# openTPM-v30.net
KiCad netlist of a schematic drawn in EAGLE
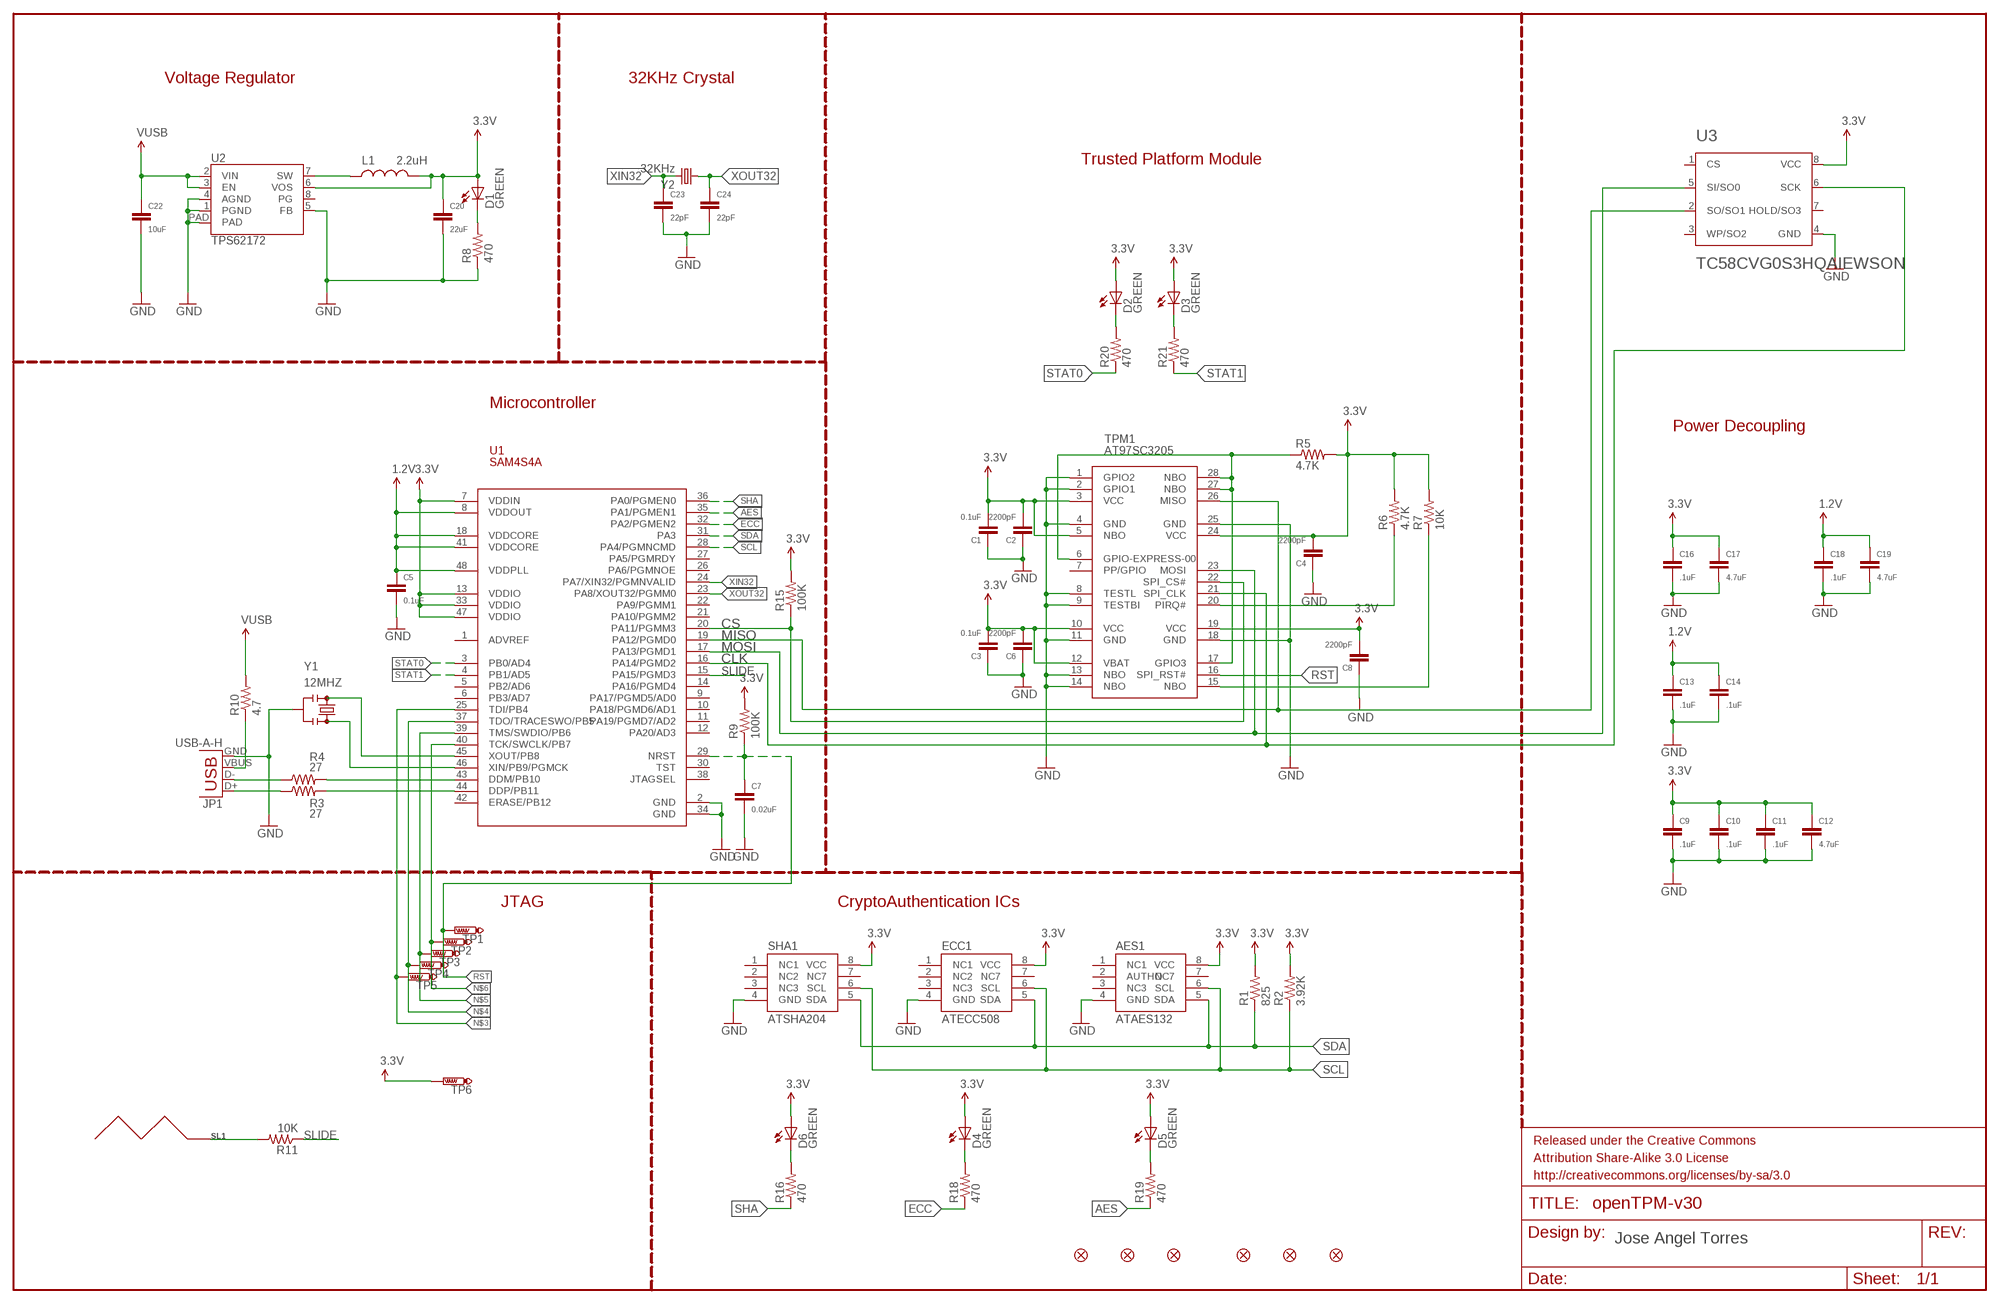
[diagram p0: schematic, sheet 1]

(export (version "E")
  (design (tool "Eeschema 10.0.6"))
  (components
    (comp (ref "AES1")
      (value "ATAES132")
      (footprint "eagle-import:CRYPTOTRONIX_SOIC8")
      (libsource (lib "eagle-import") (part "CRYPTOTRONIX_ATAES132"))
    )
    (comp (ref "C1")
      (value "0.1uF")
      (footprint "eagle-import:0402")
      (libsource (lib "eagle-import") (part "CAPACITOR.0402"))
    )
    (comp (ref "C2")
      (value "2200pF")
      (footprint "eagle-import:0402")
      (libsource (lib "eagle-import") (part "CAPACITOR.0402"))
    )
    (comp (ref "C3")
      (value "0.1uF")
      (footprint "eagle-import:0402")
      (libsource (lib "eagle-import") (part "CAPACITOR.0402"))
    )
    (comp (ref "C4")
      (value "2200pF")
      (footprint "eagle-import:0402")
      (libsource (lib "eagle-import") (part "CAPACITOR.0402"))
    )
    (comp (ref "C5")
      (value "0.1uF")
      (footprint "eagle-import:0402")
      (libsource (lib "eagle-import") (part "CAPACITOR.0402"))
    )
    (comp (ref "C6")
      (value "2200pF")
      (footprint "eagle-import:0402")
      (libsource (lib "eagle-import") (part "CAPACITOR.0402"))
    )
    (comp (ref "C7")
      (value "0.02uF")
      (footprint "eagle-import:0402")
      (libsource (lib "eagle-import") (part "CAPACITOR.0402"))
    )
    (comp (ref "C8")
      (value "2200pF")
      (footprint "eagle-import:0402")
      (libsource (lib "eagle-import") (part "CAPACITOR.0402"))
    )
    (comp (ref "C9")
      (value ".1uF")
      (footprint "eagle-import:0402")
      (libsource (lib "eagle-import") (part "CAPACITOR.0402"))
    )
    (comp (ref "C10")
      (value ".1uF")
      (footprint "eagle-import:0402")
      (libsource (lib "eagle-import") (part "CAPACITOR.0402"))
    )
    (comp (ref "C11")
      (value ".1uF")
      (footprint "eagle-import:0402")
      (libsource (lib "eagle-import") (part "CAPACITOR.0402"))
    )
    (comp (ref "C12")
      (value "4.7uF")
      (footprint "eagle-import:0402")
      (libsource (lib "eagle-import") (part "CAPACITOR.0402"))
    )
    (comp (ref "C13")
      (value ".1uF")
      (footprint "eagle-import:0402")
      (libsource (lib "eagle-import") (part "CAPACITOR.0402"))
    )
    (comp (ref "C14")
      (value ".1uF")
      (footprint "eagle-import:0402")
      (libsource (lib "eagle-import") (part "CAPACITOR.0402"))
    )
    (comp (ref "C16")
      (value ".1uF")
      (footprint "eagle-import:0402")
      (libsource (lib "eagle-import") (part "CAPACITOR.0402"))
    )
    (comp (ref "C17")
      (value "4.7uF")
      (footprint "eagle-import:0402")
      (libsource (lib "eagle-import") (part "CAPACITOR.0402"))
    )
    (comp (ref "C18")
      (value ".1uF")
      (footprint "eagle-import:0402")
      (libsource (lib "eagle-import") (part "CAPACITOR.0402"))
    )
    (comp (ref "C19")
      (value "4.7uF")
      (footprint "eagle-import:0402")
      (libsource (lib "eagle-import") (part "CAPACITOR.0402"))
    )
    (comp (ref "C20")
      (value "22uF")
      (footprint "eagle-import:0603")
      (libsource (lib "eagle-import") (part "CAPACITOR.0603"))
    )
    (comp (ref "C22")
      (value "10uF")
      (footprint "eagle-import:0402")
      (libsource (lib "eagle-import") (part "CAPACITOR.0402"))
    )
    (comp (ref "C23")
      (value "22pF")
      (footprint "eagle-import:0402")
      (libsource (lib "eagle-import") (part "CAPACITOR.0402"))
    )
    (comp (ref "C24")
      (value "22pF")
      (footprint "eagle-import:0402")
      (libsource (lib "eagle-import") (part "CAPACITOR.0402"))
    )
    (comp (ref "D1")
      (value "GREEN")
      (footprint "eagle-import:SPARKFUN-LED_LED-0603")
      (libsource (lib "eagle-import") (part "SPARKFUN-LED_LED-GREEN0603"))
    )
    (comp (ref "D2")
      (value "GREEN")
      (footprint "eagle-import:SPARKFUN-LED_LED-0603")
      (libsource (lib "eagle-import") (part "SPARKFUN-LED_LED-GREEN0603"))
    )
    (comp (ref "D3")
      (value "GREEN")
      (footprint "eagle-import:SPARKFUN-LED_LED-0603")
      (libsource (lib "eagle-import") (part "SPARKFUN-LED_LED-GREEN0603"))
    )
    (comp (ref "D4")
      (value "GREEN")
      (footprint "eagle-import:SPARKFUN-LED_LED-0603")
      (libsource (lib "eagle-import") (part "SPARKFUN-LED_LED-GREEN0603"))
    )
    (comp (ref "D5")
      (value "GREEN")
      (footprint "eagle-import:SPARKFUN-LED_LED-0603")
      (libsource (lib "eagle-import") (part "SPARKFUN-LED_LED-GREEN0603"))
    )
    (comp (ref "D6")
      (value "GREEN")
      (footprint "eagle-import:SPARKFUN-LED_LED-0603")
      (libsource (lib "eagle-import") (part "SPARKFUN-LED_LED-GREEN0603"))
    )
    (comp (ref "ECC1")
      (value "ATECC508")
      (footprint "eagle-import:CRYPTOTRONIX_SOIC8")
      (libsource (lib "eagle-import") (part "ATECC508"))
    )
    (comp (ref "FID1")
      (value "SPARKFUN-AESTHETICS_FIDUCIAL1X2")
      (footprint "eagle-import:SPARKFUN-AESTHETICS_FIDUCIAL-1X2")
      (libsource (lib "eagle-import") (part "SPARKFUN-AESTHETICS_FIDUCIAL1X2"))
    )
    (comp (ref "FID2")
      (value "SPARKFUN-AESTHETICS_FIDUCIAL1X2")
      (footprint "eagle-import:SPARKFUN-AESTHETICS_FIDUCIAL-1X2")
      (libsource (lib "eagle-import") (part "SPARKFUN-AESTHETICS_FIDUCIAL1X2"))
    )
    (comp (ref "FID3")
      (value "SPARKFUN-AESTHETICS_FIDUCIAL1X2")
      (footprint "eagle-import:SPARKFUN-AESTHETICS_FIDUCIAL-1X2")
      (libsource (lib "eagle-import") (part "SPARKFUN-AESTHETICS_FIDUCIAL1X2"))
    )
    (comp (ref "FID4")
      (value "SPARKFUN-AESTHETICS_FIDUCIAL1X2")
      (footprint "eagle-import:SPARKFUN-AESTHETICS_FIDUCIAL-1X2")
      (libsource (lib "eagle-import") (part "SPARKFUN-AESTHETICS_FIDUCIAL1X2"))
    )
    (comp (ref "FID5")
      (value "SPARKFUN-AESTHETICS_FIDUCIAL1X2")
      (footprint "eagle-import:SPARKFUN-AESTHETICS_FIDUCIAL-1X2")
      (libsource (lib "eagle-import") (part "SPARKFUN-AESTHETICS_FIDUCIAL1X2"))
    )
    (comp (ref "FID6")
      (value "SPARKFUN-AESTHETICS_FIDUCIAL1X2")
      (footprint "eagle-import:SPARKFUN-AESTHETICS_FIDUCIAL-1X2")
      (libsource (lib "eagle-import") (part "SPARKFUN-AESTHETICS_FIDUCIAL1X2"))
    )
    (comp (ref "JP1")
      (value "USB-A-H")
      (footprint "eagle-import:USB-A-H")
      (libsource (lib "eagle-import") (part "USB-A-H"))
    )
    (comp (ref "L1")
      (value "2.2uH")
      (footprint "eagle-import:C0402")
      (libsource (lib "eagle-import") (part "INDUCTOR0402"))
    )
    (comp (ref "R1")
      (value "825")
      (footprint "eagle-import:0402")
      (libsource (lib "eagle-import") (part "RESISTOR.0402"))
    )
    (comp (ref "R2")
      (value "3.92K")
      (footprint "eagle-import:0402")
      (libsource (lib "eagle-import") (part "RESISTOR.0402"))
    )
    (comp (ref "R3")
      (value "27")
      (footprint "eagle-import:0402")
      (libsource (lib "eagle-import") (part "RESISTOR.0402"))
    )
    (comp (ref "R4")
      (value "27")
      (footprint "eagle-import:0402")
      (libsource (lib "eagle-import") (part "RESISTOR.0402"))
    )
    (comp (ref "R5")
      (value "4.7K")
      (footprint "eagle-import:0402")
      (libsource (lib "eagle-import") (part "RESISTOR.0402"))
    )
    (comp (ref "R6")
      (value "4.7K")
      (footprint "eagle-import:0402")
      (libsource (lib "eagle-import") (part "RESISTOR.0402"))
    )
    (comp (ref "R7")
      (value "10K")
      (footprint "eagle-import:0402")
      (libsource (lib "eagle-import") (part "RESISTOR.0402"))
    )
    (comp (ref "R8")
      (value "470")
      (footprint "eagle-import:0402")
      (libsource (lib "eagle-import") (part "RESISTOR.0402"))
    )
    (comp (ref "R9")
      (value "100K")
      (footprint "eagle-import:0402")
      (libsource (lib "eagle-import") (part "RESISTOR.0402"))
    )
    (comp (ref "R10")
      (value "4.7")
      (footprint "eagle-import:0402")
      (libsource (lib "eagle-import") (part "RESISTOR.0402"))
    )
    (comp (ref "R11")
      (value "10K")
      (footprint "eagle-import:0402")
      (libsource (lib "eagle-import") (part "RESISTOR.0402"))
    )
    (comp (ref "R15")
      (value "100K")
      (footprint "eagle-import:0402")
      (libsource (lib "eagle-import") (part "RESISTOR.0402"))
    )
    (comp (ref "R16")
      (value "470")
      (footprint "eagle-import:0402")
      (libsource (lib "eagle-import") (part "RESISTOR.0402"))
    )
    (comp (ref "R18")
      (value "470")
      (footprint "eagle-import:0402")
      (libsource (lib "eagle-import") (part "RESISTOR.0402"))
    )
    (comp (ref "R19")
      (value "470")
      (footprint "eagle-import:0402")
      (libsource (lib "eagle-import") (part "RESISTOR.0402"))
    )
    (comp (ref "R20")
      (value "470")
      (footprint "eagle-import:0402")
      (libsource (lib "eagle-import") (part "RESISTOR.0402"))
    )
    (comp (ref "R21")
      (value "470")
      (footprint "eagle-import:0402")
      (libsource (lib "eagle-import") (part "RESISTOR.0402"))
    )
    (comp (ref "SHA1")
      (value "ATSHA204")
      (footprint "eagle-import:CRYPTOTRONIX_SOIC8")
      (libsource (lib "eagle-import") (part "CRYPTOTRONIX_ATSHA204"))
    )
    (comp (ref "SL1")
      (value "SLIDER_PASSIVE_1SEG")
      (footprint "eagle-import:SLIDER_PASSIVE_1SEG_12MM")
      (libsource (lib "eagle-import") (part "SLIDER_PASSIVE_1SEG"))
    )
    (comp (ref "TP1")
      (value "PTR1B1,27")
      (footprint "eagle-import:B1,27")
      (libsource (lib "eagle-import") (part "PTR1B1,27"))
    )
    (comp (ref "TP2")
      (value "PTR1B1,27")
      (footprint "eagle-import:B1,27")
      (libsource (lib "eagle-import") (part "PTR1B1,27"))
    )
    (comp (ref "TP3")
      (value "PTR1B1,27")
      (footprint "eagle-import:B1,27")
      (libsource (lib "eagle-import") (part "PTR1B1,27"))
    )
    (comp (ref "TP4")
      (value "PTR1B1,27")
      (footprint "eagle-import:B1,27")
      (libsource (lib "eagle-import") (part "PTR1B1,27"))
    )
    (comp (ref "TP5")
      (value "PTR1B1,27")
      (footprint "eagle-import:B1,27")
      (libsource (lib "eagle-import") (part "PTR1B1,27"))
    )
    (comp (ref "TP6")
      (value "PTR1B1,27")
      (footprint "eagle-import:B1,27")
      (libsource (lib "eagle-import") (part "PTR1B1,27"))
    )
    (comp (ref "TPM1")
      (value "AT97SC3205")
      (footprint "eagle-import:TSSOP28")
      (libsource (lib "eagle-import") (part "AT97SC3205"))
    )
    (comp (ref "U1")
      (value "SAM4S4A")
      (footprint "eagle-import:LQFP-48")
      (libsource (lib "eagle-import") (part "SAM4S4A"))
    )
    (comp (ref "U2")
      (value "TPS62172")
      (footprint "eagle-import:WSON-8-PAD")
      (libsource (lib "eagle-import") (part "TPS62172"))
    )
    (comp (ref "U3")
      (value "TC58CVG0S3HQAIEWSON")
      (footprint "eagle-import:WSON-8-PAD")
      (libsource (lib "eagle-import") (part "TC58CVG0S3HQAIEWSON"))
    )
    (comp (ref "Y1")
      (value "12MHZ")
      (footprint "eagle-import:RESONATOR-SMD")
      (libsource (lib "eagle-import") (part "RESONATOR12MHZ"))
    )
    (comp (ref "Y2")
      (value "32KHz")
      (footprint "eagle-import:CRYSTAL-32KHZ-SMD_EPSON_MC146")
      (libsource (lib "eagle-import") (part "CRYSTALEPSONMC146"))
    )
  )
  (nets
    (net (code "1") (name "/CLK") (class "Default")
      (node (ref "TPM1") (pin "21") (pinfunction "SPI_CLK_21") (pintype "bidirectional"))
      (node (ref "U1") (pin "16") (pinfunction "PA14/PGMD2_16") (pintype "bidirectional"))
      (node (ref "U3") (pin "6") (pinfunction "SCK_6") (pintype "bidirectional"))
    )
    (net (code "2") (name "/CS") (class "Default")
      (node (ref "R15") (pin "1") (pinfunction "1_1") (pintype "passive"))
      (node (ref "TPM1") (pin "22") (pinfunction "SPI_CS#_22") (pintype "power_in"))
      (node (ref "U1") (pin "20") (pinfunction "PA11/PGMM3_20") (pintype "bidirectional"))
    )
    (net (code "3") (name "/MISO") (class "Default")
      (node (ref "TPM1") (pin "26") (pinfunction "MISO_26") (pintype "power_in"))
      (node (ref "U1") (pin "19") (pinfunction "PA12/PGMD0_19") (pintype "bidirectional"))
      (node (ref "U3") (pin "2") (pinfunction "SO/SO1_2") (pintype "bidirectional"))
    )
    (net (code "4") (name "/MOSI") (class "Default")
      (node (ref "TPM1") (pin "23") (pinfunction "MOSI_23") (pintype "power_in"))
      (node (ref "U1") (pin "17") (pinfunction "PA13/PGMD1_17") (pintype "bidirectional"))
      (node (ref "U3") (pin "5") (pinfunction "SI/SO0_5") (pintype "bidirectional"))
    )
    (net (code "5") (name "/SLIDE") (class "Default")
      (node (ref "R11") (pin "1") (pinfunction "1_1") (pintype "passive"))
      (node (ref "U1") (pin "15") (pinfunction "PA15/PGMD3_15") (pintype "bidirectional"))
    )
    (net (code "6") (name "1.2V") (class "Default")
      (node (ref "C13") (pin "1") (pinfunction "1_1") (pintype "passive"))
      (node (ref "C14") (pin "1") (pinfunction "1_1") (pintype "passive"))
      (node (ref "C18") (pin "1") (pinfunction "1_1") (pintype "passive"))
      (node (ref "C19") (pin "1") (pinfunction "1_1") (pintype "passive"))
      (node (ref "C5") (pin "1") (pinfunction "1_1") (pintype "passive"))
      (node (ref "U1") (pin "18") (pinfunction "VDDCORE_18") (pintype "bidirectional"))
      (node (ref "U1") (pin "41") (pinfunction "VDDCORE_41") (pintype "bidirectional"))
      (node (ref "U1") (pin "48") (pinfunction "VDDPLL_48") (pintype "bidirectional"))
      (node (ref "U1") (pin "8") (pinfunction "VDDOUT_8") (pintype "bidirectional"))
    )
    (net (code "7") (name "3.3V") (class "Default")
      (node (ref "AES1") (pin "8") (pinfunction "VCC_8") (pintype "power_in"))
      (node (ref "C1") (pin "2") (pinfunction "2_2") (pintype "passive"))
      (node (ref "C10") (pin "1") (pinfunction "1_1") (pintype "passive"))
      (node (ref "C11") (pin "1") (pinfunction "1_1") (pintype "passive"))
      (node (ref "C12") (pin "1") (pinfunction "1_1") (pintype "passive"))
      (node (ref "C16") (pin "1") (pinfunction "1_1") (pintype "passive"))
      (node (ref "C17") (pin "1") (pinfunction "1_1") (pintype "passive"))
      (node (ref "C2") (pin "2") (pinfunction "2_2") (pintype "passive"))
      (node (ref "C20") (pin "1") (pinfunction "1_1") (pintype "passive"))
      (node (ref "C3") (pin "2") (pinfunction "2_2") (pintype "passive"))
      (node (ref "C4") (pin "2") (pinfunction "2_2") (pintype "passive"))
      (node (ref "C6") (pin "2") (pinfunction "2_2") (pintype "passive"))
      (node (ref "C8") (pin "2") (pinfunction "2_2") (pintype "passive"))
      (node (ref "C9") (pin "1") (pinfunction "1_1") (pintype "passive"))
      (node (ref "D1") (pin "A") (pinfunction "A_A") (pintype "passive"))
      (node (ref "D2") (pin "A") (pinfunction "A_A") (pintype "passive"))
      (node (ref "D3") (pin "A") (pinfunction "A_A") (pintype "passive"))
      (node (ref "D4") (pin "A") (pinfunction "A_A") (pintype "passive"))
      (node (ref "D5") (pin "A") (pinfunction "A_A") (pintype "passive"))
      (node (ref "D6") (pin "A") (pinfunction "A_A") (pintype "passive"))
      (node (ref "ECC1") (pin "8") (pinfunction "VCC_8") (pintype "power_in"))
      (node (ref "L1") (pin "2") (pinfunction "2_2") (pintype "passive"))
      (node (ref "R1") (pin "2") (pinfunction "2_2") (pintype "passive"))
      (node (ref "R15") (pin "2") (pinfunction "2_2") (pintype "passive"))
      (node (ref "R2") (pin "2") (pinfunction "2_2") (pintype "passive"))
      (node (ref "R5") (pin "2") (pinfunction "2_2") (pintype "passive"))
      (node (ref "R6") (pin "2") (pinfunction "2_2") (pintype "passive"))
      (node (ref "R7") (pin "2") (pinfunction "2_2") (pintype "passive"))
      (node (ref "R9") (pin "2") (pinfunction "2_2") (pintype "passive"))
      (node (ref "SHA1") (pin "8") (pinfunction "VCC_8") (pintype "power_in"))
      (node (ref "TP6") (pin "TP") (pinfunction "TP_TP") (pintype "input"))
      (node (ref "TPM1") (pin "10") (pinfunction "VCC_10") (pintype "power_in"))
      (node (ref "TPM1") (pin "12") (pinfunction "VBAT_12") (pintype "bidirectional"))
      (node (ref "TPM1") (pin "19") (pinfunction "VCC_19") (pintype "power_in"))
      (node (ref "TPM1") (pin "24") (pinfunction "VCC_24") (pintype "power_in"))
      (node (ref "TPM1") (pin "3") (pinfunction "VCC_3") (pintype "power_in"))
      (node (ref "TPM1") (pin "5") (pinfunction "NBO_5") (pintype "bidirectional"))
      (node (ref "U1") (pin "13") (pinfunction "VDDIO_13") (pintype "bidirectional"))
      (node (ref "U1") (pin "33") (pinfunction "VDDIO_33") (pintype "bidirectional"))
      (node (ref "U1") (pin "47") (pinfunction "VDDIO_47") (pintype "bidirectional"))
      (node (ref "U1") (pin "7") (pinfunction "VDDIN_7") (pintype "bidirectional"))
      (node (ref "U2") (pin "6") (pinfunction "VOS_6") (pintype "bidirectional"))
      (node (ref "U3") (pin "8") (pinfunction "VCC_8") (pintype "bidirectional"))
    )
    (net (code "8") (name "AES") (class "Default")
      (node (ref "R19") (pin "1") (pinfunction "1_1") (pintype "passive"))
      (node (ref "U1") (pin "35") (pinfunction "PA1/PGMEN1_35") (pintype "bidirectional"))
    )
    (net (code "9") (name "ECC") (class "Default")
      (node (ref "R18") (pin "1") (pinfunction "1_1") (pintype "passive"))
      (node (ref "U1") (pin "32") (pinfunction "PA2/PGMEN2_32") (pintype "bidirectional"))
    )
    (net (code "10") (name "GND") (class "Default")
      (node (ref "AES1") (pin "4") (pinfunction "GND_4") (pintype "power_in"))
      (node (ref "C1") (pin "1") (pinfunction "1_1") (pintype "passive"))
      (node (ref "C10") (pin "2") (pinfunction "2_2") (pintype "passive"))
      (node (ref "C11") (pin "2") (pinfunction "2_2") (pintype "passive"))
      (node (ref "C12") (pin "2") (pinfunction "2_2") (pintype "passive"))
      (node (ref "C13") (pin "2") (pinfunction "2_2") (pintype "passive"))
      (node (ref "C14") (pin "2") (pinfunction "2_2") (pintype "passive"))
      (node (ref "C16") (pin "2") (pinfunction "2_2") (pintype "passive"))
      (node (ref "C17") (pin "2") (pinfunction "2_2") (pintype "passive"))
      (node (ref "C18") (pin "2") (pinfunction "2_2") (pintype "passive"))
      (node (ref "C19") (pin "2") (pinfunction "2_2") (pintype "passive"))
      (node (ref "C2") (pin "1") (pinfunction "1_1") (pintype "passive"))
      (node (ref "C20") (pin "2") (pinfunction "2_2") (pintype "passive"))
      (node (ref "C22") (pin "2") (pinfunction "2_2") (pintype "passive"))
      (node (ref "C23") (pin "2") (pinfunction "2_2") (pintype "passive"))
      (node (ref "C24") (pin "2") (pinfunction "2_2") (pintype "passive"))
      (node (ref "C3") (pin "1") (pinfunction "1_1") (pintype "passive"))
      (node (ref "C4") (pin "1") (pinfunction "1_1") (pintype "passive"))
      (node (ref "C5") (pin "2") (pinfunction "2_2") (pintype "passive"))
      (node (ref "C6") (pin "1") (pinfunction "1_1") (pintype "passive"))
      (node (ref "C7") (pin "2") (pinfunction "2_2") (pintype "passive"))
      (node (ref "C8") (pin "1") (pinfunction "1_1") (pintype "passive"))
      (node (ref "C9") (pin "2") (pinfunction "2_2") (pintype "passive"))
      (node (ref "ECC1") (pin "4") (pinfunction "GND_4") (pintype "power_in"))
      (node (ref "JP1") (pin "GND") (pinfunction "GND_GND") (pintype "bidirectional"))
      (node (ref "R8") (pin "1") (pinfunction "1_1") (pintype "passive"))
      (node (ref "SHA1") (pin "4") (pinfunction "GND_4") (pintype "power_in"))
      (node (ref "TPM1") (pin "1") (pinfunction "GPIO2_1") (pintype "bidirectional"))
      (node (ref "TPM1") (pin "11") (pinfunction "GND_11") (pintype "power_in"))
      (node (ref "TPM1") (pin "13") (pinfunction "NBO_13") (pintype "bidirectional"))
      (node (ref "TPM1") (pin "14") (pinfunction "NBO_14") (pintype "bidirectional"))
      (node (ref "TPM1") (pin "18") (pinfunction "GND_18") (pintype "power_in"))
      (node (ref "TPM1") (pin "2") (pinfunction "GPIO1_2") (pintype "bidirectional"))
      (node (ref "TPM1") (pin "25") (pinfunction "GND_25") (pintype "power_in"))
      (node (ref "TPM1") (pin "4") (pinfunction "GND_4") (pintype "power_in"))
      (node (ref "TPM1") (pin "8") (pinfunction "TESTL_8") (pintype "bidirectional"))
      (node (ref "TPM1") (pin "9") (pinfunction "TESTBI_9") (pintype "bidirectional"))
      (node (ref "U1") (pin "2") (pinfunction "GND_2") (pintype "bidirectional"))
      (node (ref "U1") (pin "34") (pinfunction "GND_34") (pintype "bidirectional"))
      (node (ref "U2") (pin "1") (pinfunction "PGND_1") (pintype "bidirectional"))
      (node (ref "U2") (pin "4") (pinfunction "AGND_4") (pintype "bidirectional"))
      (node (ref "U2") (pin "5") (pinfunction "FB_5") (pintype "bidirectional"))
      (node (ref "U2") (pin "PAD") (pinfunction "PAD_PAD") (pintype "bidirectional"))
      (node (ref "U3") (pin "4") (pinfunction "GND_4") (pintype "bidirectional"))
      (node (ref "Y1") (pin "2") (pinfunction "2_2") (pintype "passive"))
    )
    (net (code "11") (name "N$3") (class "Default")
      (node (ref "TP5") (pin "TP") (pinfunction "TP_TP") (pintype "input"))
      (node (ref "U1") (pin "25") (pinfunction "TDI/PB4_25") (pintype "bidirectional"))
    )
    (net (code "12") (name "N$4") (class "Default")
      (node (ref "TP4") (pin "TP") (pinfunction "TP_TP") (pintype "input"))
      (node (ref "U1") (pin "37") (pinfunction "TDO/TRACESWO/PB5_37") (pintype "bidirectional"))
    )
    (net (code "13") (name "N$5") (class "Default")
      (node (ref "TP3") (pin "TP") (pinfunction "TP_TP") (pintype "input"))
      (node (ref "U1") (pin "39") (pinfunction "TMS/SWDIO/PB6_39") (pintype "bidirectional"))
    )
    (net (code "14") (name "N$6") (class "Default")
      (node (ref "TP2") (pin "TP") (pinfunction "TP_TP") (pintype "input"))
      (node (ref "U1") (pin "40") (pinfunction "TCK/SWCLK/PB7_40") (pintype "bidirectional"))
    )
    (net (code "15") (name "Net-(D1-PadC)") (class "Default")
      (node (ref "D1") (pin "C") (pinfunction "C_C") (pintype "passive"))
      (node (ref "R8") (pin "2") (pinfunction "2_2") (pintype "passive"))
    )
    (net (code "16") (name "Net-(D2-PadC)") (class "Default")
      (node (ref "D2") (pin "C") (pinfunction "C_C") (pintype "passive"))
      (node (ref "R20") (pin "2") (pinfunction "2_2") (pintype "passive"))
    )
    (net (code "17") (name "Net-(D3-PadC)") (class "Default")
      (node (ref "D3") (pin "C") (pinfunction "C_C") (pintype "passive"))
      (node (ref "R21") (pin "2") (pinfunction "2_2") (pintype "passive"))
    )
    (net (code "18") (name "Net-(D4-PadC)") (class "Default")
      (node (ref "D4") (pin "C") (pinfunction "C_C") (pintype "passive"))
      (node (ref "R18") (pin "2") (pinfunction "2_2") (pintype "passive"))
    )
    (net (code "19") (name "Net-(D5-PadC)") (class "Default")
      (node (ref "D5") (pin "C") (pinfunction "C_C") (pintype "passive"))
      (node (ref "R19") (pin "2") (pinfunction "2_2") (pintype "passive"))
    )
    (net (code "20") (name "Net-(D6-PadC)") (class "Default")
      (node (ref "D6") (pin "C") (pinfunction "C_C") (pintype "passive"))
      (node (ref "R16") (pin "2") (pinfunction "2_2") (pintype "passive"))
    )
    (net (code "21") (name "Net-(JP1-PadD+)") (class "Default")
      (node (ref "JP1") (pin "D+") (pinfunction "D+_D+") (pintype "bidirectional"))
      (node (ref "R3") (pin "1") (pinfunction "1_1") (pintype "passive"))
    )
    (net (code "22") (name "Net-(JP1-PadD-)") (class "Default")
      (node (ref "JP1") (pin "D-") (pinfunction "D-_D-") (pintype "bidirectional"))
      (node (ref "R4") (pin "1") (pinfunction "1_1") (pintype "passive"))
    )
    (net (code "23") (name "Net-(JP1-PadVBUS)") (class "Default")
      (node (ref "JP1") (pin "VBUS") (pinfunction "VBUS_VBUS") (pintype "bidirectional"))
      (node (ref "R10") (pin "1") (pinfunction "1_1") (pintype "passive"))
    )
    (net (code "24") (name "Net-(R7-Pad1)") (class "Default")
      (node (ref "R7") (pin "1") (pinfunction "1_1") (pintype "passive"))
      (node (ref "TPM1") (pin "15") (pinfunction "NBO_15") (pintype "bidirectional"))
    )
    (net (code "25") (name "Net-(SL1-SL1)") (class "Default")
      (node (ref "R11") (pin "2") (pinfunction "2_2") (pintype "passive"))
      (node (ref "SL1") (pin "S1") (pinfunction "SL1_S1") (pintype "passive"))
    )
    (net (code "26") (name "Net-(TPM1-GPIO-EXPRESS-00)") (class "Default")
      (node (ref "R5") (pin "1") (pinfunction "1_1") (pintype "passive"))
      (node (ref "TPM1") (pin "17") (pinfunction "GPIO3_17") (pintype "power_in"))
      (node (ref "TPM1") (pin "27") (pinfunction "NBO_27") (pintype "bidirectional"))
      (node (ref "TPM1") (pin "28") (pinfunction "NBO_28") (pintype "bidirectional"))
      (node (ref "TPM1") (pin "6") (pinfunction "GPIO-EXPRESS-00_6") (pintype "power_in"))
    )
    (net (code "27") (name "Net-(TPM1-PIRQ#)") (class "Default")
      (node (ref "R6") (pin "1") (pinfunction "1_1") (pintype "passive"))
      (node (ref "TPM1") (pin "20") (pinfunction "PIRQ#_20") (pintype "power_in"))
    )
    (net (code "28") (name "Net-(U1-DDM{slash}PB10)") (class "Default")
      (node (ref "R4") (pin "2") (pinfunction "2_2") (pintype "passive"))
      (node (ref "U1") (pin "43") (pinfunction "DDM/PB10_43") (pintype "bidirectional"))
    )
    (net (code "29") (name "Net-(U1-DDP{slash}PB11)") (class "Default")
      (node (ref "R3") (pin "2") (pinfunction "2_2") (pintype "passive"))
      (node (ref "U1") (pin "44") (pinfunction "DDP/PB11_44") (pintype "bidirectional"))
    )
    (net (code "30") (name "Net-(U1-XIN{slash}PB9{slash}PGMCK)") (class "Default")
      (node (ref "U1") (pin "46") (pinfunction "XIN/PB9/PGMCK_46") (pintype "bidirectional"))
      (node (ref "Y1") (pin "3") (pinfunction "3_3") (pintype "passive"))
    )
    (net (code "31") (name "Net-(U1-XOUT{slash}PB8)") (class "Default")
      (node (ref "U1") (pin "45") (pinfunction "XOUT/PB8_45") (pintype "bidirectional"))
      (node (ref "Y1") (pin "1") (pinfunction "1_1") (pintype "passive"))
    )
    (net (code "32") (name "Net-(U2-SW)") (class "Default")
      (node (ref "L1") (pin "1") (pinfunction "1_1") (pintype "passive"))
      (node (ref "U2") (pin "7") (pinfunction "SW_7") (pintype "bidirectional"))
    )
    (net (code "33") (name "RST") (class "Default")
      (node (ref "C7") (pin "1") (pinfunction "1_1") (pintype "passive"))
      (node (ref "R9") (pin "1") (pinfunction "1_1") (pintype "passive"))
      (node (ref "TP1") (pin "TP") (pinfunction "TP_TP") (pintype "input"))
      (node (ref "TPM1") (pin "16") (pinfunction "SPI_RST#_16") (pintype "bidirectional"))
      (node (ref "U1") (pin "29") (pinfunction "NRST_29") (pintype "bidirectional"))
    )
    (net (code "34") (name "SCL") (class "Default")
      (node (ref "AES1") (pin "6") (pinfunction "SCL_6") (pintype "bidirectional"))
      (node (ref "ECC1") (pin "6") (pinfunction "SCL_6") (pintype "bidirectional"))
      (node (ref "R2") (pin "1") (pinfunction "1_1") (pintype "passive"))
      (node (ref "SHA1") (pin "6") (pinfunction "SCL_6") (pintype "bidirectional"))
      (node (ref "U1") (pin "28") (pinfunction "PA4/PGMNCMD_28") (pintype "bidirectional"))
    )
    (net (code "35") (name "SDA") (class "Default")
      (node (ref "AES1") (pin "5") (pinfunction "SDA_5") (pintype "bidirectional"))
      (node (ref "ECC1") (pin "5") (pinfunction "SDA_5") (pintype "bidirectional"))
      (node (ref "R1") (pin "1") (pinfunction "1_1") (pintype "passive"))
      (node (ref "SHA1") (pin "5") (pinfunction "SDA_5") (pintype "bidirectional"))
      (node (ref "U1") (pin "31") (pinfunction "PA3_31") (pintype "bidirectional"))
    )
    (net (code "36") (name "SHA") (class "Default")
      (node (ref "R16") (pin "1") (pinfunction "1_1") (pintype "passive"))
      (node (ref "U1") (pin "36") (pinfunction "PA0/PGMEN0_36") (pintype "bidirectional"))
    )
    (net (code "37") (name "STAT0") (class "Default")
      (node (ref "R20") (pin "1") (pinfunction "1_1") (pintype "passive"))
      (node (ref "U1") (pin "3") (pinfunction "PB0/AD4_3") (pintype "bidirectional"))
    )
    (net (code "38") (name "STAT1") (class "Default")
      (node (ref "R21") (pin "1") (pinfunction "1_1") (pintype "passive"))
      (node (ref "U1") (pin "4") (pinfunction "PB1/AD5_4") (pintype "bidirectional"))
    )
    (net (code "39") (name "VUSB") (class "Default")
      (node (ref "C22") (pin "1") (pinfunction "1_1") (pintype "passive"))
      (node (ref "R10") (pin "2") (pinfunction "2_2") (pintype "passive"))
      (node (ref "U2") (pin "2") (pinfunction "VIN_2") (pintype "bidirectional"))
      (node (ref "U2") (pin "3") (pinfunction "EN_3") (pintype "bidirectional"))
    )
    (net (code "40") (name "XIN32") (class "Default")
      (node (ref "C23") (pin "1") (pinfunction "1_1") (pintype "passive"))
      (node (ref "U1") (pin "24") (pinfunction "PA7/XIN32/PGMNVALID_24") (pintype "bidirectional"))
      (node (ref "Y2") (pin "P$1") (pinfunction "2_P$1") (pintype "passive"))
    )
    (net (code "41") (name "XOUT32") (class "Default")
      (node (ref "C24") (pin "1") (pinfunction "1_1") (pintype "passive"))
      (node (ref "U1") (pin "23") (pinfunction "PA8/XOUT32/PGMM0_23") (pintype "bidirectional"))
      (node (ref "Y2") (pin "P$2") (pinfunction "1_P$2") (pintype "passive"))
    )
    (net (code "42") (name "unconnected-(AES1-AUTHO-Pad2)") (class "Default")
      (node (ref "AES1") (pin "2") (pinfunction "AUTHO_2") (pintype "bidirectional"))
    )
    (net (code "43") (name "unconnected-(AES1-NC1-Pad1)") (class "Default")
      (node (ref "AES1") (pin "1") (pinfunction "NC1_1") (pintype "no_connect"))
    )
    (net (code "44") (name "unconnected-(AES1-NC3-Pad3)") (class "Default")
      (node (ref "AES1") (pin "3") (pinfunction "NC3_3") (pintype "no_connect"))
    )
    (net (code "45") (name "unconnected-(AES1-NC7-Pad7)") (class "Default")
      (node (ref "AES1") (pin "7") (pinfunction "NC7_7") (pintype "no_connect"))
    )
    (net (code "46") (name "unconnected-(ECC1-NC1-Pad1)") (class "Default")
      (node (ref "ECC1") (pin "1") (pinfunction "NC1_1") (pintype "bidirectional"))
    )
    (net (code "47") (name "unconnected-(ECC1-NC2-Pad2)") (class "Default")
      (node (ref "ECC1") (pin "2") (pinfunction "NC2_2") (pintype "no_connect"))
    )
    (net (code "48") (name "unconnected-(ECC1-NC3-Pad3)") (class "Default")
      (node (ref "ECC1") (pin "3") (pinfunction "NC3_3") (pintype "no_connect"))
    )
    (net (code "49") (name "unconnected-(ECC1-NC7-Pad7)") (class "Default")
      (node (ref "ECC1") (pin "7") (pinfunction "NC7_7") (pintype "no_connect"))
    )
    (net (code "50") (name "unconnected-(SHA1-NC1-Pad1)") (class "Default")
      (node (ref "SHA1") (pin "1") (pinfunction "NC1_1") (pintype "no_connect"))
    )
    (net (code "51") (name "unconnected-(SHA1-NC2-Pad2)") (class "Default")
      (node (ref "SHA1") (pin "2") (pinfunction "NC2_2") (pintype "no_connect"))
    )
    (net (code "52") (name "unconnected-(SHA1-NC3-Pad3)") (class "Default")
      (node (ref "SHA1") (pin "3") (pinfunction "NC3_3") (pintype "no_connect"))
    )
    (net (code "53") (name "unconnected-(SHA1-NC7-Pad7)") (class "Default")
      (node (ref "SHA1") (pin "7") (pinfunction "NC7_7") (pintype "no_connect"))
    )
    (net (code "54") (name "unconnected-(TPM1-PP{slash}GPIO-Pad7)") (class "Default")
      (node (ref "TPM1") (pin "7") (pinfunction "PP/GPIO_7") (pintype "bidirectional"))
    )
    (net (code "55") (name "unconnected-(U1-ADVREF-Pad1)") (class "Default")
      (node (ref "U1") (pin "1") (pinfunction "ADVREF_1") (pintype "bidirectional"))
    )
    (net (code "56") (name "unconnected-(U1-ERASE{slash}PB12-Pad42)") (class "Default")
      (node (ref "U1") (pin "42") (pinfunction "ERASE/PB12_42") (pintype "bidirectional"))
    )
    (net (code "57") (name "unconnected-(U1-JTAGSEL-Pad38)") (class "Default")
      (node (ref "U1") (pin "38") (pinfunction "JTAGSEL_38") (pintype "bidirectional"))
    )
    (net (code "58") (name "unconnected-(U1-PA5{slash}PGMRDY-Pad27)") (class "Default")
      (node (ref "U1") (pin "27") (pinfunction "PA5/PGMRDY_27") (pintype "bidirectional"))
    )
    (net (code "59") (name "unconnected-(U1-PA6{slash}PGMNOE-Pad26)") (class "Default")
      (node (ref "U1") (pin "26") (pinfunction "PA6/PGMNOE_26") (pintype "bidirectional"))
    )
    (net (code "60") (name "unconnected-(U1-PA9{slash}PGMM1-Pad22)") (class "Default")
      (node (ref "U1") (pin "22") (pinfunction "PA9/PGMM1_22") (pintype "bidirectional"))
    )
    (net (code "61") (name "unconnected-(U1-PA10{slash}PGMM2-Pad21)") (class "Default")
      (node (ref "U1") (pin "21") (pinfunction "PA10/PGMM2_21") (pintype "bidirectional"))
    )
    (net (code "62") (name "unconnected-(U1-PA16{slash}PGMD4-Pad14)") (class "Default")
      (node (ref "U1") (pin "14") (pinfunction "PA16/PGMD4_14") (pintype "bidirectional"))
    )
    (net (code "63") (name "unconnected-(U1-PA17{slash}PGMD5{slash}AD0-Pad9)") (class "Default")
      (node (ref "U1") (pin "9") (pinfunction "PA17/PGMD5/AD0_9") (pintype "bidirectional"))
    )
    (net (code "64") (name "unconnected-(U1-PA18{slash}PGMD6{slash}AD1-Pad10)") (class "Default")
      (node (ref "U1") (pin "10") (pinfunction "PA18/PGMD6/AD1_10") (pintype "bidirectional"))
    )
    (net (code "65") (name "unconnected-(U1-PA19{slash}PGMD7{slash}AD2-Pad11)") (class "Default")
      (node (ref "U1") (pin "11") (pinfunction "PA19/PGMD7/AD2_11") (pintype "bidirectional"))
    )
    (net (code "66") (name "unconnected-(U1-PA20{slash}AD3-Pad12)") (class "Default")
      (node (ref "U1") (pin "12") (pinfunction "PA20/AD3_12") (pintype "bidirectional"))
    )
    (net (code "67") (name "unconnected-(U1-PB2{slash}AD6-Pad5)") (class "Default")
      (node (ref "U1") (pin "5") (pinfunction "PB2/AD6_5") (pintype "bidirectional"))
    )
    (net (code "68") (name "unconnected-(U1-PB3{slash}AD7-Pad6)") (class "Default")
      (node (ref "U1") (pin "6") (pinfunction "PB3/AD7_6") (pintype "bidirectional"))
    )
    (net (code "69") (name "unconnected-(U1-TST-Pad30)") (class "Default")
      (node (ref "U1") (pin "30") (pinfunction "TST_30") (pintype "bidirectional"))
    )
    (net (code "70") (name "unconnected-(U2-PG-Pad8)") (class "Default")
      (node (ref "U2") (pin "8") (pinfunction "PG_8") (pintype "bidirectional"))
    )
    (net (code "71") (name "unconnected-(U3-CS-Pad1)") (class "Default")
      (node (ref "U3") (pin "1") (pinfunction "CS_1") (pintype "bidirectional"))
    )
    (net (code "72") (name "unconnected-(U3-HOLD{slash}SO3-Pad7)") (class "Default")
      (node (ref "U3") (pin "7") (pinfunction "HOLD/SO3_7") (pintype "bidirectional"))
    )
    (net (code "73") (name "unconnected-(U3-WP{slash}SO2-Pad3)") (class "Default")
      (node (ref "U3") (pin "3") (pinfunction "WP/SO2_3") (pintype "bidirectional"))
    )
  )
)
